# ArduinoUnoShield.net
KiCad netlist of a schematic drawn in Altium Designer
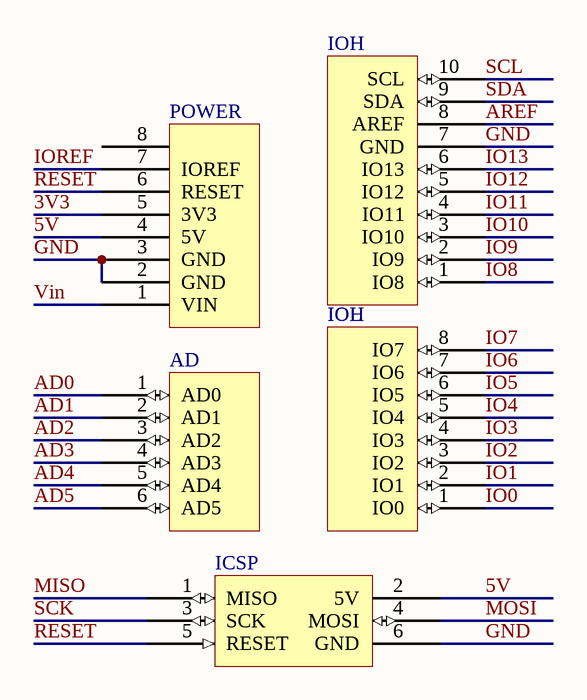
[diagram p0: ArduinoUnoShield.SchDoc]

(export (version "E")
  (design (tool "Eeschema 10.0.6"))
  (components
    (comp (ref "AD")
      (value "AD")
      (footprint "Header:Header 6x1 8.5mm")
      (libsource (lib "Header") (part "AD"))
    )
    (comp (ref "ICSP") (value "ICSP") (footprint "ICSP") (libsource (lib "Header") (part "ICSP")))
    (comp (ref "IOH")
      (value "IOH")
      (footprint "Header:Header 10x1 8.5mm")
      (libsource (lib "Header") (part "IOH"))
    )
    (comp (ref "IOL") (value "IOL") (footprint "Header 8x1 8.5mm") (libsource (lib "Header") (part "IOL")))
    (comp (ref "POWER")
      (value "POWER_UNO")
      (footprint "Header 8x1 8.5mm")
      (libsource (lib "Header") (part "POWER_UNO"))
    )
  )
  (nets
    (net (code "1") (name "/3V3") (class "Default")
      (node (ref "POWER") (pin "5") (pinfunction "3V3_5") (pintype "power_in"))
    )
    (net (code "2") (name "/5V") (class "Default")
      (node (ref "ICSP") (pin "2") (pinfunction "5V_2") (pintype "power_in"))
      (node (ref "POWER") (pin "4") (pinfunction "5V_4") (pintype "power_in"))
    )
    (net (code "4") (name "/AD0") (class "Default")
      (node (ref "AD") (pin "1") (pinfunction "AD0_1") (pintype "bidirectional"))
    )
    (net (code "5") (name "/AD1") (class "Default")
      (node (ref "AD") (pin "2") (pinfunction "AD1_2") (pintype "bidirectional"))
    )
    (net (code "6") (name "/AD2") (class "Default")
      (node (ref "AD") (pin "3") (pinfunction "AD2_3") (pintype "bidirectional"))
    )
    (net (code "7") (name "/AD3") (class "Default")
      (node (ref "AD") (pin "4") (pinfunction "AD3_4") (pintype "bidirectional"))
    )
    (net (code "8") (name "/AD4") (class "Default")
      (node (ref "AD") (pin "5") (pinfunction "AD4_5") (pintype "bidirectional"))
    )
    (net (code "9") (name "/AD5") (class "Default")
      (node (ref "AD") (pin "6") (pinfunction "AD5_6") (pintype "bidirectional"))
    )
    (net (code "10") (name "/AREF") (class "Default")
      (node (ref "IOH") (pin "8") (pinfunction "AREF_8") (pintype "passive"))
    )
    (net (code "11") (name "/GND") (class "Default")
      (node (ref "ICSP") (pin "6") (pinfunction "GND_6") (pintype "power_in"))
      (node (ref "IOH") (pin "7") (pinfunction "GND_7") (pintype "power_in"))
      (node (ref "POWER") (pin "2") (pinfunction "GND_2") (pintype "power_in"))
      (node (ref "POWER") (pin "3") (pinfunction "GND_3") (pintype "power_in"))
    )
    (net (code "12") (name "/IO0") (class "Default")
      (node (ref "IOL") (pin "1") (pinfunction "IO0_1") (pintype "bidirectional"))
    )
    (net (code "13") (name "/IO1") (class "Default")
      (node (ref "IOL") (pin "2") (pinfunction "IO1_2") (pintype "bidirectional"))
    )
    (net (code "14") (name "/IO2") (class "Default")
      (node (ref "IOL") (pin "3") (pinfunction "IO2_3") (pintype "bidirectional"))
    )
    (net (code "15") (name "/IO3") (class "Default")
      (node (ref "IOL") (pin "4") (pinfunction "IO3_4") (pintype "bidirectional"))
    )
    (net (code "16") (name "/IO4") (class "Default")
      (node (ref "IOL") (pin "5") (pinfunction "IO4_5") (pintype "bidirectional"))
    )
    (net (code "17") (name "/IO5") (class "Default")
      (node (ref "IOL") (pin "6") (pinfunction "IO5_6") (pintype "bidirectional"))
    )
    (net (code "18") (name "/IO6") (class "Default")
      (node (ref "IOL") (pin "7") (pinfunction "IO6_7") (pintype "bidirectional"))
    )
    (net (code "19") (name "/IO7") (class "Default")
      (node (ref "IOL") (pin "8") (pinfunction "IO7_8") (pintype "bidirectional"))
    )
    (net (code "20") (name "/IO8") (class "Default")
      (node (ref "IOH") (pin "1") (pinfunction "IO8_1") (pintype "bidirectional"))
    )
    (net (code "21") (name "/IO9") (class "Default")
      (node (ref "IOH") (pin "2") (pinfunction "IO9_2") (pintype "bidirectional"))
    )
    (net (code "22") (name "/IO10") (class "Default")
      (node (ref "IOH") (pin "3") (pinfunction "IO10_3") (pintype "bidirectional"))
    )
    (net (code "23") (name "/IO11") (class "Default")
      (node (ref "IOH") (pin "4") (pinfunction "IO11_4") (pintype "bidirectional"))
    )
    (net (code "24") (name "/IO12") (class "Default")
      (node (ref "IOH") (pin "5") (pinfunction "IO12_5") (pintype "bidirectional"))
    )
    (net (code "25") (name "/IO13") (class "Default")
      (node (ref "IOH") (pin "6") (pinfunction "IO13_6") (pintype "bidirectional"))
    )
    (net (code "26") (name "/IOREF") (class "Default")
      (node (ref "POWER") (pin "7") (pinfunction "IOREF_7") (pintype "power_in"))
    )
    (net (code "27") (name "/MISO") (class "Default")
      (node (ref "ICSP") (pin "1") (pinfunction "MISO_1") (pintype "bidirectional"))
    )
    (net (code "28") (name "/MOSI") (class "Default")
      (node (ref "ICSP") (pin "4") (pinfunction "MOSI_4") (pintype "bidirectional"))
    )
    (net (code "29") (name "/RESET") (class "Default")
      (node (ref "ICSP") (pin "5") (pinfunction "RESET_5") (pintype "input"))
      (node (ref "POWER") (pin "6") (pinfunction "RESET_6") (pintype "passive"))
    )
    (net (code "30") (name "/SCK") (class "Default")
      (node (ref "ICSP") (pin "3") (pinfunction "SCK_3") (pintype "bidirectional"))
    )
    (net (code "31") (name "/SCL") (class "Default")
      (node (ref "IOH") (pin "10") (pinfunction "SCL_10") (pintype "bidirectional"))
    )
    (net (code "32") (name "/SDA") (class "Default")
      (node (ref "IOH") (pin "9") (pinfunction "SDA_9") (pintype "bidirectional"))
    )
    (net (code "33") (name "/Vin") (class "Default")
      (node (ref "POWER") (pin "1") (pinfunction "VIN_1") (pintype "power_in"))
    )
    (net (code "34") (name "unconnected-(POWER-Pad8)") (class "Default")
      (node (ref "POWER") (pin "8") (pintype "passive"))
    )
  )
)
